# main_full.net
KiCad netlist of a schematic drawn in EAGLE
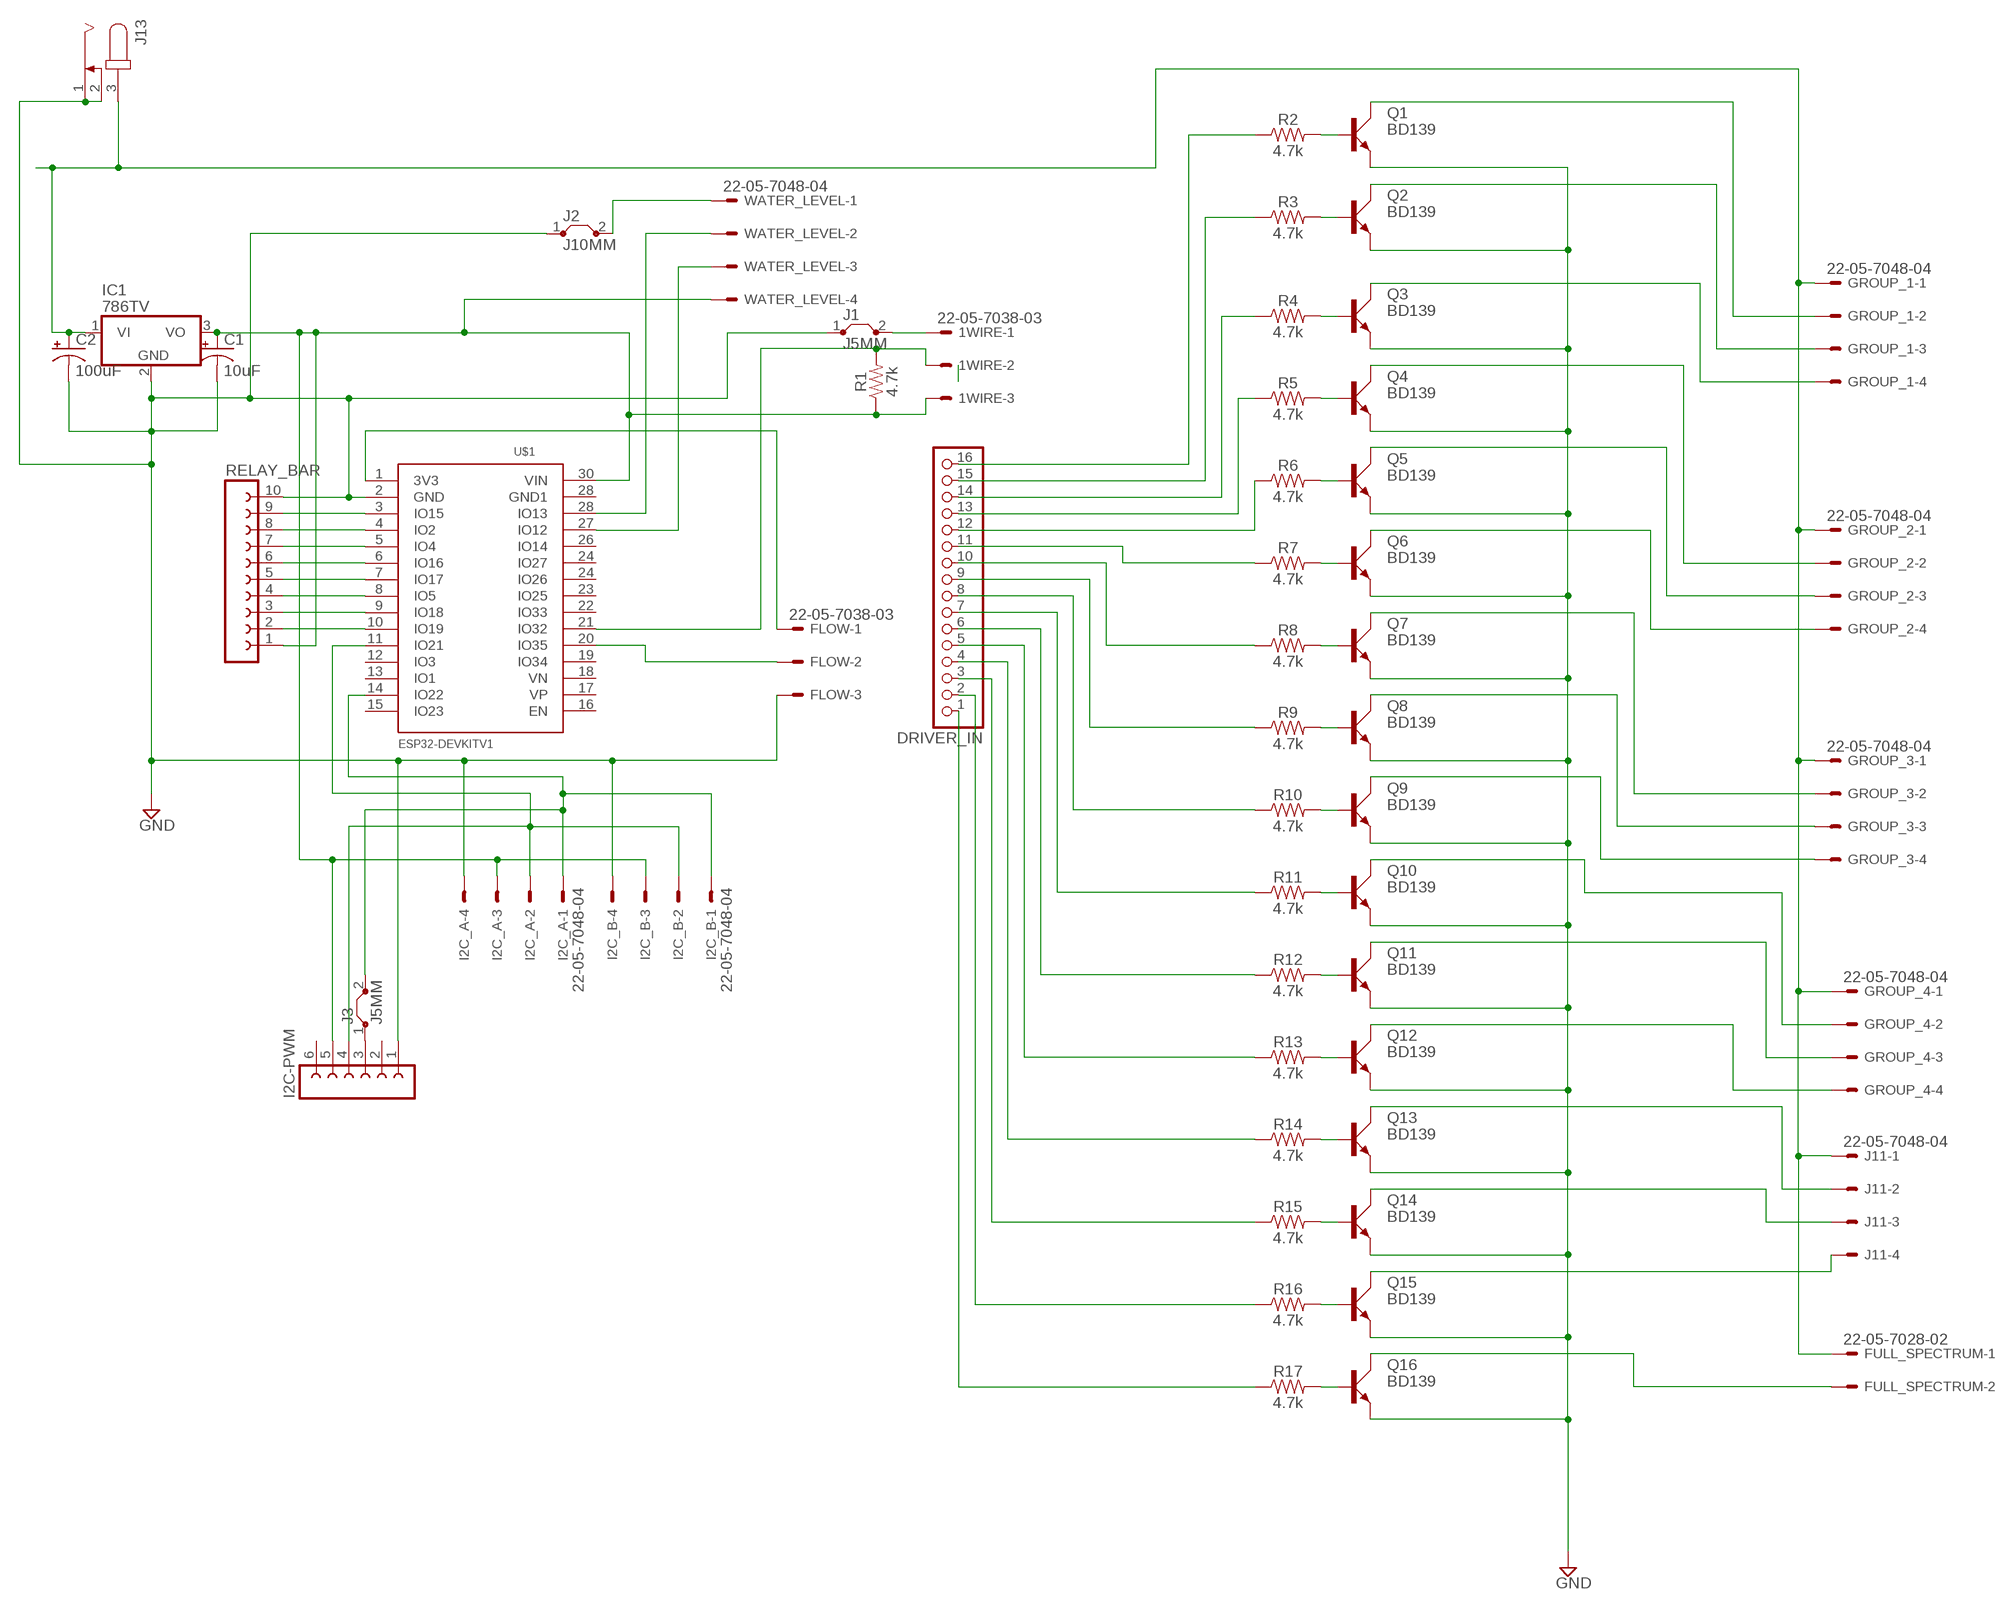
[diagram p0: schematic, sheet 1]

(export (version "E")
  (design (tool "Eeschema 10.0.6"))
  (components
    (comp (ref "1WIRE")
      (value "22-05-7038-03")
      (footprint "eagle-import:7395-03")
      (fields (field (name "MF") "MOLEX"))
      (libsource (lib "eagle-import") (part "22-?-0305-7038"))
    )
    (comp (ref "C1")
      (value "10uF")
      (footprint "eagle-import:CPOL-RADIAL-2.5MM-5MM")
      (libsource (lib "eagle-import") (part "10UF-POLAR-RADIAL-2.5MM-25V-20%"))
    )
    (comp (ref "C2")
      (value "100uF")
      (footprint "eagle-import:CPOL-RADIAL-2.5MM-6.5MM")
      (libsource (lib "eagle-import") (part "100UF-POLAR-RADIAL-2.5MM-25V-20%"))
    )
    (comp (ref "DRIVER_IN")
      (value "PINHD-1X16/90")
      (footprint "eagle-import:1X16_90")
      (libsource (lib "eagle-import") (part "PINHD-1X16/90"))
    )
    (comp (ref "FLOW")
      (value "22-05-7038-03")
      (footprint "eagle-import:7395-03")
      (fields (field (name "MF") "MOLEX"))
      (libsource (lib "eagle-import") (part "22-?-0305-7038"))
    )
    (comp (ref "FULL_SPECTRUM")
      (value "22-05-7028-02")
      (footprint "eagle-import:7395-02")
      (fields (field (name "MF") "MOLEX"))
      (libsource (lib "eagle-import") (part "22-?-0205-7028"))
    )
    (comp (ref "GROUP_1")
      (value "22-05-7048-04")
      (footprint "eagle-import:7395-04")
      (fields (field (name "MF") "MOLEX"))
      (libsource (lib "eagle-import") (part "22-?-0405-7048"))
    )
    (comp (ref "GROUP_2")
      (value "22-05-7048-04")
      (footprint "eagle-import:7395-04")
      (fields (field (name "MF") "MOLEX"))
      (libsource (lib "eagle-import") (part "22-?-0405-7048"))
    )
    (comp (ref "GROUP_3")
      (value "22-05-7048-04")
      (footprint "eagle-import:7395-04")
      (fields (field (name "MF") "MOLEX"))
      (libsource (lib "eagle-import") (part "22-?-0405-7048"))
    )
    (comp (ref "GROUP_4")
      (value "22-05-7048-04")
      (footprint "eagle-import:7395-04")
      (fields (field (name "MF") "MOLEX"))
      (libsource (lib "eagle-import") (part "22-?-0405-7048"))
    )
    (comp (ref "I2C-PWM")
      (value "FE06W")
      (footprint "eagle-import:FE06W")
      (libsource (lib "eagle-import") (part "FE06W"))
    )
    (comp (ref "I2C_A")
      (value "22-05-7048-04")
      (footprint "eagle-import:7395-04")
      (fields (field (name "MF") "MOLEX"))
      (libsource (lib "eagle-import") (part "22-?-0405-7048"))
    )
    (comp (ref "I2C_B")
      (value "22-05-7048-04")
      (footprint "eagle-import:7395-04")
      (fields (field (name "MF") "MOLEX"))
      (libsource (lib "eagle-import") (part "22-?-0405-7048"))
    )
    (comp (ref "IC1")
      (value "786TV")
      (footprint "eagle-import:TO220V")
      (libsource (lib "eagle-import") (part "78TV6"))
    )
    (comp (ref "J1")
      (value "J5MM")
      (footprint "eagle-import:05")
      (libsource (lib "eagle-import") (part "J5MM"))
    )
    (comp (ref "J2")
      (value "J10MM")
      (footprint "eagle-import:10")
      (libsource (lib "eagle-import") (part "J10MM"))
    )
    (comp (ref "J3")
      (value "J5MM")
      (footprint "eagle-import:05")
      (libsource (lib "eagle-import") (part "J5MM"))
    )
    (comp (ref "J11")
      (value "22-05-7048-04")
      (footprint "eagle-import:7395-04")
      (fields (field (name "MF") "MOLEX"))
      (libsource (lib "eagle-import") (part "22-?-0405-7048"))
    )
    (comp (ref "J13")
      (value "JACK-PLUG0")
      (footprint "eagle-import:SPC4077")
      (libsource (lib "eagle-import") (part "JACK-PLUG0"))
    )
    (comp (ref "Q1")
      (value "BD139")
      (footprint "eagle-import:TO126AV")
      (libsource (lib "eagle-import") (part "BD139"))
    )
    (comp (ref "Q2")
      (value "BD139")
      (footprint "eagle-import:TO126AV")
      (libsource (lib "eagle-import") (part "BD139"))
    )
    (comp (ref "Q3")
      (value "BD139")
      (footprint "eagle-import:TO126AV")
      (libsource (lib "eagle-import") (part "BD139"))
    )
    (comp (ref "Q4")
      (value "BD139")
      (footprint "eagle-import:TO126AV")
      (libsource (lib "eagle-import") (part "BD139"))
    )
    (comp (ref "Q5")
      (value "BD139")
      (footprint "eagle-import:TO126AV")
      (libsource (lib "eagle-import") (part "BD139"))
    )
    (comp (ref "Q6")
      (value "BD139")
      (footprint "eagle-import:TO126AV")
      (libsource (lib "eagle-import") (part "BD139"))
    )
    (comp (ref "Q7")
      (value "BD139")
      (footprint "eagle-import:TO126AV")
      (libsource (lib "eagle-import") (part "BD139"))
    )
    (comp (ref "Q8")
      (value "BD139")
      (footprint "eagle-import:TO126AV")
      (libsource (lib "eagle-import") (part "BD139"))
    )
    (comp (ref "Q9")
      (value "BD139")
      (footprint "eagle-import:TO126AV")
      (libsource (lib "eagle-import") (part "BD139"))
    )
    (comp (ref "Q10")
      (value "BD139")
      (footprint "eagle-import:TO126AV")
      (libsource (lib "eagle-import") (part "BD139"))
    )
    (comp (ref "Q11")
      (value "BD139")
      (footprint "eagle-import:TO126AV")
      (libsource (lib "eagle-import") (part "BD139"))
    )
    (comp (ref "Q12")
      (value "BD139")
      (footprint "eagle-import:TO126AV")
      (libsource (lib "eagle-import") (part "BD139"))
    )
    (comp (ref "Q13")
      (value "BD139")
      (footprint "eagle-import:TO126AV")
      (libsource (lib "eagle-import") (part "BD139"))
    )
    (comp (ref "Q14")
      (value "BD139")
      (footprint "eagle-import:TO126AV")
      (libsource (lib "eagle-import") (part "BD139"))
    )
    (comp (ref "Q15")
      (value "BD139")
      (footprint "eagle-import:TO126AV")
      (libsource (lib "eagle-import") (part "BD139"))
    )
    (comp (ref "Q16")
      (value "BD139")
      (footprint "eagle-import:TO126AV")
      (libsource (lib "eagle-import") (part "BD139"))
    )
    (comp (ref "R1")
      (value "4.7k")
      (footprint "eagle-import:0603")
      (libsource (lib "eagle-import") (part "4.7KOHM-0603-1/10W-1%"))
    )
    (comp (ref "R2")
      (value "4.7k")
      (footprint "eagle-import:0603")
      (libsource (lib "eagle-import") (part "4.7KOHM-0603-1/10W-1%"))
    )
    (comp (ref "R3")
      (value "4.7k")
      (footprint "eagle-import:0603")
      (libsource (lib "eagle-import") (part "4.7KOHM-0603-1/10W-1%"))
    )
    (comp (ref "R4")
      (value "4.7k")
      (footprint "eagle-import:0603")
      (libsource (lib "eagle-import") (part "4.7KOHM-0603-1/10W-1%"))
    )
    (comp (ref "R5")
      (value "4.7k")
      (footprint "eagle-import:0603")
      (libsource (lib "eagle-import") (part "4.7KOHM-0603-1/10W-1%"))
    )
    (comp (ref "R6")
      (value "4.7k")
      (footprint "eagle-import:0603")
      (libsource (lib "eagle-import") (part "4.7KOHM-0603-1/10W-1%"))
    )
    (comp (ref "R7")
      (value "4.7k")
      (footprint "eagle-import:0603")
      (libsource (lib "eagle-import") (part "4.7KOHM-0603-1/10W-1%"))
    )
    (comp (ref "R8")
      (value "4.7k")
      (footprint "eagle-import:0603")
      (libsource (lib "eagle-import") (part "4.7KOHM-0603-1/10W-1%"))
    )
    (comp (ref "R9")
      (value "4.7k")
      (footprint "eagle-import:0603")
      (libsource (lib "eagle-import") (part "4.7KOHM-0603-1/10W-1%"))
    )
    (comp (ref "R10")
      (value "4.7k")
      (footprint "eagle-import:0603")
      (libsource (lib "eagle-import") (part "4.7KOHM-0603-1/10W-1%"))
    )
    (comp (ref "R11")
      (value "4.7k")
      (footprint "eagle-import:0603")
      (libsource (lib "eagle-import") (part "4.7KOHM-0603-1/10W-1%"))
    )
    (comp (ref "R12")
      (value "4.7k")
      (footprint "eagle-import:0603")
      (libsource (lib "eagle-import") (part "4.7KOHM-0603-1/10W-1%"))
    )
    (comp (ref "R13")
      (value "4.7k")
      (footprint "eagle-import:0603")
      (libsource (lib "eagle-import") (part "4.7KOHM-0603-1/10W-1%"))
    )
    (comp (ref "R14")
      (value "4.7k")
      (footprint "eagle-import:0603")
      (libsource (lib "eagle-import") (part "4.7KOHM-0603-1/10W-1%"))
    )
    (comp (ref "R15")
      (value "4.7k")
      (footprint "eagle-import:0603")
      (libsource (lib "eagle-import") (part "4.7KOHM-0603-1/10W-1%"))
    )
    (comp (ref "R16")
      (value "4.7k")
      (footprint "eagle-import:0603")
      (libsource (lib "eagle-import") (part "4.7KOHM-0603-1/10W-1%"))
    )
    (comp (ref "R17")
      (value "4.7k")
      (footprint "eagle-import:0603")
      (libsource (lib "eagle-import") (part "4.7KOHM-0603-1/10W-1%"))
    )
    (comp (ref "RELAY_BAR")
      (value "FE10W")
      (footprint "eagle-import:FE10W")
      (libsource (lib "eagle-import") (part "FE10W"))
    )
    (comp (ref "U$1")
      (value "ESP32DEVKITV1")
      (footprint "eagle-import:ESP32-DEVKITV1")
      (libsource (lib "eagle-import") (part "ESP32DEVKITV1"))
    )
    (comp (ref "WATER_LEVEL")
      (value "22-05-7048-04")
      (footprint "eagle-import:7395-04")
      (fields (field (name "MF") "MOLEX"))
      (libsource (lib "eagle-import") (part "22-?-0405-7048"))
    )
  )
  (nets
    (net (code "1") (name "GND") (class "Default")
      (node (ref "C1") (pin "2") (pinfunction "-_2") (pintype "passive"))
      (node (ref "C2") (pin "2") (pinfunction "-_2") (pintype "passive"))
      (node (ref "FLOW") (pin "3") (pinfunction "S_3") (pintype "passive"))
      (node (ref "I2C-PWM") (pin "1") (pinfunction "1_1") (pintype "passive"))
      (node (ref "I2C_A") (pin "4") (pinfunction "S_4") (pintype "passive"))
      (node (ref "I2C_B") (pin "4") (pinfunction "S_4") (pintype "passive"))
      (node (ref "IC1") (pin "2") (pinfunction "GND_2") (pintype "passive"))
      (node (ref "J1") (pin "1") (pinfunction "1_1") (pintype "passive"))
      (node (ref "J13") (pin "1") (pinfunction "1_1") (pintype "passive"))
      (node (ref "J13") (pin "2") (pinfunction "2_2") (pintype "passive"))
      (node (ref "J2") (pin "1") (pinfunction "1_1") (pintype "passive"))
      (node (ref "Q1") (pin "E") (pinfunction "E_E") (pintype "passive"))
      (node (ref "Q10") (pin "E") (pinfunction "E_E") (pintype "passive"))
      (node (ref "Q11") (pin "E") (pinfunction "E_E") (pintype "passive"))
      (node (ref "Q12") (pin "E") (pinfunction "E_E") (pintype "passive"))
      (node (ref "Q13") (pin "E") (pinfunction "E_E") (pintype "passive"))
      (node (ref "Q14") (pin "E") (pinfunction "E_E") (pintype "passive"))
      (node (ref "Q15") (pin "E") (pinfunction "E_E") (pintype "passive"))
      (node (ref "Q16") (pin "E") (pinfunction "E_E") (pintype "passive"))
      (node (ref "Q2") (pin "E") (pinfunction "E_E") (pintype "passive"))
      (node (ref "Q3") (pin "E") (pinfunction "E_E") (pintype "passive"))
      (node (ref "Q4") (pin "E") (pinfunction "E_E") (pintype "passive"))
      (node (ref "Q5") (pin "E") (pinfunction "E_E") (pintype "passive"))
      (node (ref "Q6") (pin "E") (pinfunction "E_E") (pintype "passive"))
      (node (ref "Q7") (pin "E") (pinfunction "E_E") (pintype "passive"))
      (node (ref "Q8") (pin "E") (pinfunction "E_E") (pintype "passive"))
      (node (ref "Q9") (pin "E") (pinfunction "E_E") (pintype "passive"))
      (node (ref "RELAY_BAR") (pin "10") (pinfunction "10_10") (pintype "passive"))
      (node (ref "U$1") (pin "2") (pinfunction "GND_2") (pintype "bidirectional"))
    )
    (net (code "2") (name "Net-(1WIREA-S)") (class "Default")
      (node (ref "1WIRE") (pin "1") (pinfunction "S_1") (pintype "passive"))
      (node (ref "J1") (pin "2") (pinfunction "2_2") (pintype "passive"))
    )
    (net (code "3") (name "Net-(1WIREB-S)") (class "Default")
      (node (ref "1WIRE") (pin "2") (pinfunction "S_2") (pintype "passive"))
      (node (ref "R1") (pin "2") (pinfunction "2_2") (pintype "passive"))
      (node (ref "U$1") (pin "21") (pinfunction "IO32_21") (pintype "bidirectional"))
    )
    (net (code "4") (name "Net-(1WIREC-S)") (class "Default")
      (node (ref "1WIRE") (pin "3") (pinfunction "S_3") (pintype "passive"))
      (node (ref "C1") (pin "1") (pinfunction "+_1") (pintype "passive"))
      (node (ref "I2C-PWM") (pin "5") (pinfunction "5_5") (pintype "passive"))
      (node (ref "I2C_A") (pin "3") (pinfunction "S_3") (pintype "passive"))
      (node (ref "I2C_B") (pin "3") (pinfunction "S_3") (pintype "passive"))
      (node (ref "IC1") (pin "3") (pinfunction "VO_3") (pintype "passive"))
      (node (ref "R1") (pin "1") (pinfunction "1_1") (pintype "passive"))
      (node (ref "RELAY_BAR") (pin "1") (pinfunction "1_1") (pintype "passive"))
      (node (ref "U$1") (pin "30") (pinfunction "VIN_30") (pintype "bidirectional"))
      (node (ref "WATER_LEVEL") (pin "4") (pinfunction "S_4") (pintype "passive"))
    )
    (net (code "5") (name "Net-(C2-+)") (class "Default")
      (node (ref "C2") (pin "1") (pinfunction "+_1") (pintype "passive"))
      (node (ref "FULL_SPECTRUM") (pin "1") (pinfunction "S_1") (pintype "passive"))
      (node (ref "GROUP_1") (pin "1") (pinfunction "S_1") (pintype "passive"))
      (node (ref "GROUP_2") (pin "1") (pinfunction "S_1") (pintype "passive"))
      (node (ref "GROUP_3") (pin "1") (pinfunction "S_1") (pintype "passive"))
      (node (ref "GROUP_4") (pin "1") (pinfunction "S_1") (pintype "passive"))
      (node (ref "IC1") (pin "1") (pinfunction "VI_1") (pintype "input"))
      (node (ref "J11") (pin "1") (pinfunction "S_1") (pintype "passive"))
      (node (ref "J13") (pin "3") (pinfunction "3_3") (pintype "passive"))
    )
    (net (code "6") (name "Net-(DRIVER_IN-Pad1)") (class "Default")
      (node (ref "DRIVER_IN") (pin "1") (pinfunction "1_1") (pintype "passive"))
      (node (ref "R17") (pin "1") (pinfunction "1_1") (pintype "passive"))
    )
    (net (code "7") (name "Net-(DRIVER_IN-Pad2)") (class "Default")
      (node (ref "DRIVER_IN") (pin "2") (pinfunction "2_2") (pintype "passive"))
      (node (ref "R16") (pin "1") (pinfunction "1_1") (pintype "passive"))
    )
    (net (code "8") (name "Net-(DRIVER_IN-Pad3)") (class "Default")
      (node (ref "DRIVER_IN") (pin "3") (pinfunction "3_3") (pintype "passive"))
      (node (ref "R15") (pin "1") (pinfunction "1_1") (pintype "passive"))
    )
    (net (code "9") (name "Net-(DRIVER_IN-Pad4)") (class "Default")
      (node (ref "DRIVER_IN") (pin "4") (pinfunction "4_4") (pintype "passive"))
      (node (ref "R14") (pin "1") (pinfunction "1_1") (pintype "passive"))
    )
    (net (code "10") (name "Net-(DRIVER_IN-Pad5)") (class "Default")
      (node (ref "DRIVER_IN") (pin "5") (pinfunction "5_5") (pintype "passive"))
      (node (ref "R13") (pin "1") (pinfunction "1_1") (pintype "passive"))
    )
    (net (code "11") (name "Net-(DRIVER_IN-Pad6)") (class "Default")
      (node (ref "DRIVER_IN") (pin "6") (pinfunction "6_6") (pintype "passive"))
      (node (ref "R12") (pin "1") (pinfunction "1_1") (pintype "passive"))
    )
    (net (code "12") (name "Net-(DRIVER_IN-Pad7)") (class "Default")
      (node (ref "DRIVER_IN") (pin "7") (pinfunction "7_7") (pintype "passive"))
      (node (ref "R11") (pin "1") (pinfunction "1_1") (pintype "passive"))
    )
    (net (code "13") (name "Net-(DRIVER_IN-Pad8)") (class "Default")
      (node (ref "DRIVER_IN") (pin "8") (pinfunction "8_8") (pintype "passive"))
      (node (ref "R10") (pin "1") (pinfunction "1_1") (pintype "passive"))
    )
    (net (code "14") (name "Net-(DRIVER_IN-Pad9)") (class "Default")
      (node (ref "DRIVER_IN") (pin "9") (pinfunction "9_9") (pintype "passive"))
      (node (ref "R9") (pin "1") (pinfunction "1_1") (pintype "passive"))
    )
    (net (code "15") (name "Net-(DRIVER_IN-Pad10)") (class "Default")
      (node (ref "DRIVER_IN") (pin "10") (pinfunction "10_10") (pintype "passive"))
      (node (ref "R8") (pin "1") (pinfunction "1_1") (pintype "passive"))
    )
    (net (code "16") (name "Net-(DRIVER_IN-Pad11)") (class "Default")
      (node (ref "DRIVER_IN") (pin "11") (pinfunction "11_11") (pintype "passive"))
      (node (ref "R7") (pin "1") (pinfunction "1_1") (pintype "passive"))
    )
    (net (code "17") (name "Net-(DRIVER_IN-Pad12)") (class "Default")
      (node (ref "DRIVER_IN") (pin "12") (pinfunction "12_12") (pintype "passive"))
      (node (ref "R6") (pin "1") (pinfunction "1_1") (pintype "passive"))
    )
    (net (code "18") (name "Net-(DRIVER_IN-Pad13)") (class "Default")
      (node (ref "DRIVER_IN") (pin "13") (pinfunction "13_13") (pintype "passive"))
      (node (ref "R5") (pin "1") (pinfunction "1_1") (pintype "passive"))
    )
    (net (code "19") (name "Net-(DRIVER_IN-Pad14)") (class "Default")
      (node (ref "DRIVER_IN") (pin "14") (pinfunction "14_14") (pintype "passive"))
      (node (ref "R4") (pin "1") (pinfunction "1_1") (pintype "passive"))
    )
    (net (code "20") (name "Net-(DRIVER_IN-Pad15)") (class "Default")
      (node (ref "DRIVER_IN") (pin "15") (pinfunction "15_15") (pintype "passive"))
      (node (ref "R3") (pin "1") (pinfunction "1_1") (pintype "passive"))
    )
    (net (code "21") (name "Net-(DRIVER_IN-Pad16)") (class "Default")
      (node (ref "DRIVER_IN") (pin "16") (pinfunction "16_16") (pintype "passive"))
      (node (ref "R2") (pin "1") (pinfunction "1_1") (pintype "passive"))
    )
    (net (code "22") (name "Net-(FLOWA-S)") (class "Default")
      (node (ref "FLOW") (pin "1") (pinfunction "S_1") (pintype "passive"))
      (node (ref "U$1") (pin "1") (pinfunction "3V3_1") (pintype "bidirectional"))
    )
    (net (code "23") (name "Net-(FLOWB-S)") (class "Default")
      (node (ref "FLOW") (pin "2") (pinfunction "S_2") (pintype "passive"))
      (node (ref "U$1") (pin "20") (pinfunction "IO35_20") (pintype "bidirectional"))
    )
    (net (code "24") (name "Net-(FULL_SPECTRUMB-S)") (class "Default")
      (node (ref "FULL_SPECTRUM") (pin "2") (pinfunction "S_2") (pintype "passive"))
      (node (ref "Q16") (pin "C") (pinfunction "C_C") (pintype "passive"))
    )
    (net (code "25") (name "Net-(GROUP_1B-S)") (class "Default")
      (node (ref "GROUP_1") (pin "2") (pinfunction "S_2") (pintype "passive"))
      (node (ref "Q1") (pin "C") (pinfunction "C_C") (pintype "passive"))
    )
    (net (code "26") (name "Net-(GROUP_1C-S)") (class "Default")
      (node (ref "GROUP_1") (pin "3") (pinfunction "S_3") (pintype "passive"))
      (node (ref "Q2") (pin "C") (pinfunction "C_C") (pintype "passive"))
    )
    (net (code "27") (name "Net-(GROUP_1D-S)") (class "Default")
      (node (ref "GROUP_1") (pin "4") (pinfunction "S_4") (pintype "passive"))
      (node (ref "Q3") (pin "C") (pinfunction "C_C") (pintype "passive"))
    )
    (net (code "28") (name "Net-(GROUP_2B-S)") (class "Default")
      (node (ref "GROUP_2") (pin "2") (pinfunction "S_2") (pintype "passive"))
      (node (ref "Q4") (pin "C") (pinfunction "C_C") (pintype "passive"))
    )
    (net (code "29") (name "Net-(GROUP_2C-S)") (class "Default")
      (node (ref "GROUP_2") (pin "3") (pinfunction "S_3") (pintype "passive"))
      (node (ref "Q5") (pin "C") (pinfunction "C_C") (pintype "passive"))
    )
    (net (code "30") (name "Net-(GROUP_2D-S)") (class "Default")
      (node (ref "GROUP_2") (pin "4") (pinfunction "S_4") (pintype "passive"))
      (node (ref "Q6") (pin "C") (pinfunction "C_C") (pintype "passive"))
    )
    (net (code "31") (name "Net-(GROUP_3B-S)") (class "Default")
      (node (ref "GROUP_3") (pin "2") (pinfunction "S_2") (pintype "passive"))
      (node (ref "Q7") (pin "C") (pinfunction "C_C") (pintype "passive"))
    )
    (net (code "32") (name "Net-(GROUP_3C-S)") (class "Default")
      (node (ref "GROUP_3") (pin "3") (pinfunction "S_3") (pintype "passive"))
      (node (ref "Q8") (pin "C") (pinfunction "C_C") (pintype "passive"))
    )
    (net (code "33") (name "Net-(GROUP_3D-S)") (class "Default")
      (node (ref "GROUP_3") (pin "4") (pinfunction "S_4") (pintype "passive"))
      (node (ref "Q9") (pin "C") (pinfunction "C_C") (pintype "passive"))
    )
    (net (code "34") (name "Net-(GROUP_4B-S)") (class "Default")
      (node (ref "GROUP_4") (pin "2") (pinfunction "S_2") (pintype "passive"))
      (node (ref "Q10") (pin "C") (pinfunction "C_C") (pintype "passive"))
    )
    (net (code "35") (name "Net-(GROUP_4C-S)") (class "Default")
      (node (ref "GROUP_4") (pin "3") (pinfunction "S_3") (pintype "passive"))
      (node (ref "Q11") (pin "C") (pinfunction "C_C") (pintype "passive"))
    )
    (net (code "36") (name "Net-(GROUP_4D-S)") (class "Default")
      (node (ref "GROUP_4") (pin "4") (pinfunction "S_4") (pintype "passive"))
      (node (ref "Q12") (pin "C") (pinfunction "C_C") (pintype "passive"))
    )
    (net (code "37") (name "Net-(I2C-PWM-Pad3)") (class "Default")
      (node (ref "I2C-PWM") (pin "3") (pinfunction "3_3") (pintype "passive"))
      (node (ref "J3") (pin "1") (pinfunction "1_1") (pintype "passive"))
    )
    (net (code "38") (name "Net-(I2C_AA-S)") (class "Default")
      (node (ref "I2C_A") (pin "1") (pinfunction "S_1") (pintype "passive"))
      (node (ref "I2C_B") (pin "1") (pinfunction "S_1") (pintype "passive"))
      (node (ref "J3") (pin "2") (pinfunction "2_2") (pintype "passive"))
      (node (ref "U$1") (pin "14") (pinfunction "IO22_14") (pintype "bidirectional"))
    )
    (net (code "39") (name "Net-(I2C_AB-S)") (class "Default")
      (node (ref "I2C-PWM") (pin "4") (pinfunction "4_4") (pintype "passive"))
      (node (ref "I2C_A") (pin "2") (pinfunction "S_2") (pintype "passive"))
      (node (ref "I2C_B") (pin "2") (pinfunction "S_2") (pintype "passive"))
      (node (ref "U$1") (pin "11") (pinfunction "IO21_11") (pintype "bidirectional"))
    )
    (net (code "40") (name "Net-(J11B-S)") (class "Default")
      (node (ref "J11") (pin "2") (pinfunction "S_2") (pintype "passive"))
      (node (ref "Q13") (pin "C") (pinfunction "C_C") (pintype "passive"))
    )
    (net (code "41") (name "Net-(J11C-S)") (class "Default")
      (node (ref "J11") (pin "3") (pinfunction "S_3") (pintype "passive"))
      (node (ref "Q14") (pin "C") (pinfunction "C_C") (pintype "passive"))
    )
    (net (code "42") (name "Net-(J11D-S)") (class "Default")
      (node (ref "J11") (pin "4") (pinfunction "S_4") (pintype "passive"))
      (node (ref "Q15") (pin "C") (pinfunction "C_C") (pintype "passive"))
    )
    (net (code "43") (name "Net-(Q1-PadB)") (class "Default")
      (node (ref "Q1") (pin "B") (pinfunction "B_B") (pintype "passive"))
      (node (ref "R2") (pin "2") (pinfunction "2_2") (pintype "passive"))
    )
    (net (code "44") (name "Net-(Q2-PadB)") (class "Default")
      (node (ref "Q2") (pin "B") (pinfunction "B_B") (pintype "passive"))
      (node (ref "R3") (pin "2") (pinfunction "2_2") (pintype "passive"))
    )
    (net (code "45") (name "Net-(Q3-PadB)") (class "Default")
      (node (ref "Q3") (pin "B") (pinfunction "B_B") (pintype "passive"))
      (node (ref "R4") (pin "2") (pinfunction "2_2") (pintype "passive"))
    )
    (net (code "46") (name "Net-(Q4-PadB)") (class "Default")
      (node (ref "Q4") (pin "B") (pinfunction "B_B") (pintype "passive"))
      (node (ref "R5") (pin "2") (pinfunction "2_2") (pintype "passive"))
    )
    (net (code "47") (name "Net-(Q5-PadB)") (class "Default")
      (node (ref "Q5") (pin "B") (pinfunction "B_B") (pintype "passive"))
      (node (ref "R6") (pin "2") (pinfunction "2_2") (pintype "passive"))
    )
    (net (code "48") (name "Net-(Q6-PadB)") (class "Default")
      (node (ref "Q6") (pin "B") (pinfunction "B_B") (pintype "passive"))
      (node (ref "R7") (pin "2") (pinfunction "2_2") (pintype "passive"))
    )
    (net (code "49") (name "Net-(Q7-PadB)") (class "Default")
      (node (ref "Q7") (pin "B") (pinfunction "B_B") (pintype "passive"))
      (node (ref "R8") (pin "2") (pinfunction "2_2") (pintype "passive"))
    )
    (net (code "50") (name "Net-(Q8-PadB)") (class "Default")
      (node (ref "Q8") (pin "B") (pinfunction "B_B") (pintype "passive"))
      (node (ref "R9") (pin "2") (pinfunction "2_2") (pintype "passive"))
    )
    (net (code "51") (name "Net-(Q9-PadB)") (class "Default")
      (node (ref "Q9") (pin "B") (pinfunction "B_B") (pintype "passive"))
      (node (ref "R10") (pin "2") (pinfunction "2_2") (pintype "passive"))
    )
    (net (code "52") (name "Net-(Q10-PadB)") (class "Default")
      (node (ref "Q10") (pin "B") (pinfunction "B_B") (pintype "passive"))
      (node (ref "R11") (pin "2") (pinfunction "2_2") (pintype "passive"))
    )
    (net (code "53") (name "Net-(Q11-PadB)") (class "Default")
      (node (ref "Q11") (pin "B") (pinfunction "B_B") (pintype "passive"))
      (node (ref "R12") (pin "2") (pinfunction "2_2") (pintype "passive"))
    )
    (net (code "54") (name "Net-(Q12-PadB)") (class "Default")
      (node (ref "Q12") (pin "B") (pinfunction "B_B") (pintype "passive"))
      (node (ref "R13") (pin "2") (pinfunction "2_2") (pintype "passive"))
    )
    (net (code "55") (name "Net-(Q13-PadB)") (class "Default")
      (node (ref "Q13") (pin "B") (pinfunction "B_B") (pintype "passive"))
      (node (ref "R14") (pin "2") (pinfunction "2_2") (pintype "passive"))
    )
    (net (code "56") (name "Net-(Q14-PadB)") (class "Default")
      (node (ref "Q14") (pin "B") (pinfunction "B_B") (pintype "passive"))
      (node (ref "R15") (pin "2") (pinfunction "2_2") (pintype "passive"))
    )
    (net (code "57") (name "Net-(Q15-PadB)") (class "Default")
      (node (ref "Q15") (pin "B") (pinfunction "B_B") (pintype "passive"))
      (node (ref "R16") (pin "2") (pinfunction "2_2") (pintype "passive"))
    )
    (net (code "58") (name "Net-(Q16-PadB)") (class "Default")
      (node (ref "Q16") (pin "B") (pinfunction "B_B") (pintype "passive"))
      (node (ref "R17") (pin "2") (pinfunction "2_2") (pintype "passive"))
    )
    (net (code "59") (name "Net-(U$1-IO2)") (class "Default")
      (node (ref "RELAY_BAR") (pin "8") (pinfunction "8_8") (pintype "passive"))
      (node (ref "U$1") (pin "4") (pinfunction "IO2_4") (pintype "bidirectional"))
    )
    (net (code "60") (name "Net-(U$1-IO4)") (class "Default")
      (node (ref "RELAY_BAR") (pin "7") (pinfunction "7_7") (pintype "passive"))
      (node (ref "U$1") (pin "5") (pinfunction "IO4_5") (pintype "bidirectional"))
    )
    (net (code "61") (name "Net-(U$1-IO5)") (class "Default")
      (node (ref "RELAY_BAR") (pin "4") (pinfunction "4_4") (pintype "passive"))
      (node (ref "U$1") (pin "8") (pinfunction "IO5_8") (pintype "bidirectional"))
    )
    (net (code "62") (name "Net-(U$1-IO12)") (class "Default")
      (node (ref "U$1") (pin "27") (pinfunction "IO12_27") (pintype "bidirectional"))
      (node (ref "WATER_LEVEL") (pin "3") (pinfunction "S_3") (pintype "passive"))
    )
    (net (code "63") (name "Net-(U$1-IO13)") (class "Default")
      (node (ref "U$1") (pin "28") (pinfunction "IO13_28") (pintype "bidirectional"))
      (node (ref "WATER_LEVEL") (pin "2") (pinfunction "S_2") (pintype "passive"))
    )
    (net (code "64") (name "Net-(U$1-IO15)") (class "Default")
      (node (ref "RELAY_BAR") (pin "9") (pinfunction "9_9") (pintype "passive"))
      (node (ref "U$1") (pin "3") (pinfunction "IO15_3") (pintype "bidirectional"))
    )
    (net (code "65") (name "Net-(U$1-IO16)") (class "Default")
      (node (ref "RELAY_BAR") (pin "6") (pinfunction "6_6") (pintype "passive"))
      (node (ref "U$1") (pin "6") (pinfunction "IO16_6") (pintype "bidirectional"))
    )
    (net (code "66") (name "Net-(U$1-IO17)") (class "Default")
      (node (ref "RELAY_BAR") (pin "5") (pinfunction "5_5") (pintype "passive"))
      (node (ref "U$1") (pin "7") (pinfunction "IO17_7") (pintype "bidirectional"))
    )
    (net (code "67") (name "Net-(U$1-IO18)") (class "Default")
      (node (ref "RELAY_BAR") (pin "3") (pinfunction "3_3") (pintype "passive"))
      (node (ref "U$1") (pin "9") (pinfunction "IO18_9") (pintype "bidirectional"))
    )
    (net (code "68") (name "Net-(U$1-IO19)") (class "Default")
      (node (ref "RELAY_BAR") (pin "2") (pinfunction "2_2") (pintype "passive"))
      (node (ref "U$1") (pin "10") (pinfunction "IO19_10") (pintype "bidirectional"))
    )
    (net (code "69") (name "Net-(WATER_LEVELA-S)") (class "Default")
      (node (ref "J2") (pin "2") (pinfunction "2_2") (pintype "passive"))
      (node (ref "WATER_LEVEL") (pin "1") (pinfunction "S_1") (pintype "passive"))
    )
    (net (code "70") (name "unconnected-(I2C-PWM-Pad2)") (class "Default")
      (node (ref "I2C-PWM") (pin "2") (pinfunction "2_2") (pintype "passive"))
    )
    (net (code "71") (name "unconnected-(I2C-PWM-Pad6)") (class "Default")
      (node (ref "I2C-PWM") (pin "6") (pinfunction "6_6") (pintype "passive"))
    )
    (net (code "72") (name "unconnected-(U$1-EN-Pad16)") (class "Default")
      (node (ref "U$1") (pin "16") (pinfunction "EN_16") (pintype "bidirectional"))
    )
    (net (code "73") (name "unconnected-(U$1-GND1-Pad28)") (class "Default")
      (node (ref "U$1") (pin "28") (pinfunction "GND1_28") (pintype "bidirectional"))
    )
    (net (code "74") (name "unconnected-(U$1-IO1-Pad13)") (class "Default")
      (node (ref "U$1") (pin "13") (pinfunction "IO1_13") (pintype "bidirectional"))
    )
    (net (code "75") (name "unconnected-(U$1-IO3-Pad12)") (class "Default")
      (node (ref "U$1") (pin "12") (pinfunction "IO3_12") (pintype "bidirectional"))
    )
    (net (code "76") (name "unconnected-(U$1-IO14-Pad26)") (class "Default")
      (node (ref "U$1") (pin "26") (pinfunction "IO14_26") (pintype "bidirectional"))
    )
    (net (code "77") (name "unconnected-(U$1-IO23-Pad15)") (class "Default")
      (node (ref "U$1") (pin "15") (pinfunction "IO23_15") (pintype "bidirectional"))
    )
    (net (code "78") (name "unconnected-(U$1-IO25-Pad23)") (class "Default")
      (node (ref "U$1") (pin "23") (pinfunction "IO25_23") (pintype "bidirectional"))
    )
    (net (code "79") (name "unconnected-(U$1-IO26-Pad24)") (class "Default")
      (node (ref "U$1") (pin "24") (pinfunction "IO26_24") (pintype "bidirectional"))
    )
    (net (code "80") (name "unconnected-(U$1-IO27-Pad24)") (class "Default")
      (node (ref "U$1") (pin "24") (pinfunction "IO27_24") (pintype "bidirectional"))
    )
    (net (code "81") (name "unconnected-(U$1-IO33-Pad22)") (class "Default")
      (node (ref "U$1") (pin "22") (pinfunction "IO33_22") (pintype "bidirectional"))
    )
    (net (code "82") (name "unconnected-(U$1-IO34-Pad19)") (class "Default")
      (node (ref "U$1") (pin "19") (pinfunction "IO34_19") (pintype "bidirectional"))
    )
    (net (code "83") (name "unconnected-(U$1-VN-Pad18)") (class "Default")
      (node (ref "U$1") (pin "18") (pinfunction "VN_18") (pintype "bidirectional"))
    )
    (net (code "84") (name "unconnected-(U$1-VP-Pad17)") (class "Default")
      (node (ref "U$1") (pin "17") (pinfunction "VP_17") (pintype "bidirectional"))
    )
  )
)
